# design.net
KiCad netlist of a schematic drawn in Altium Designer
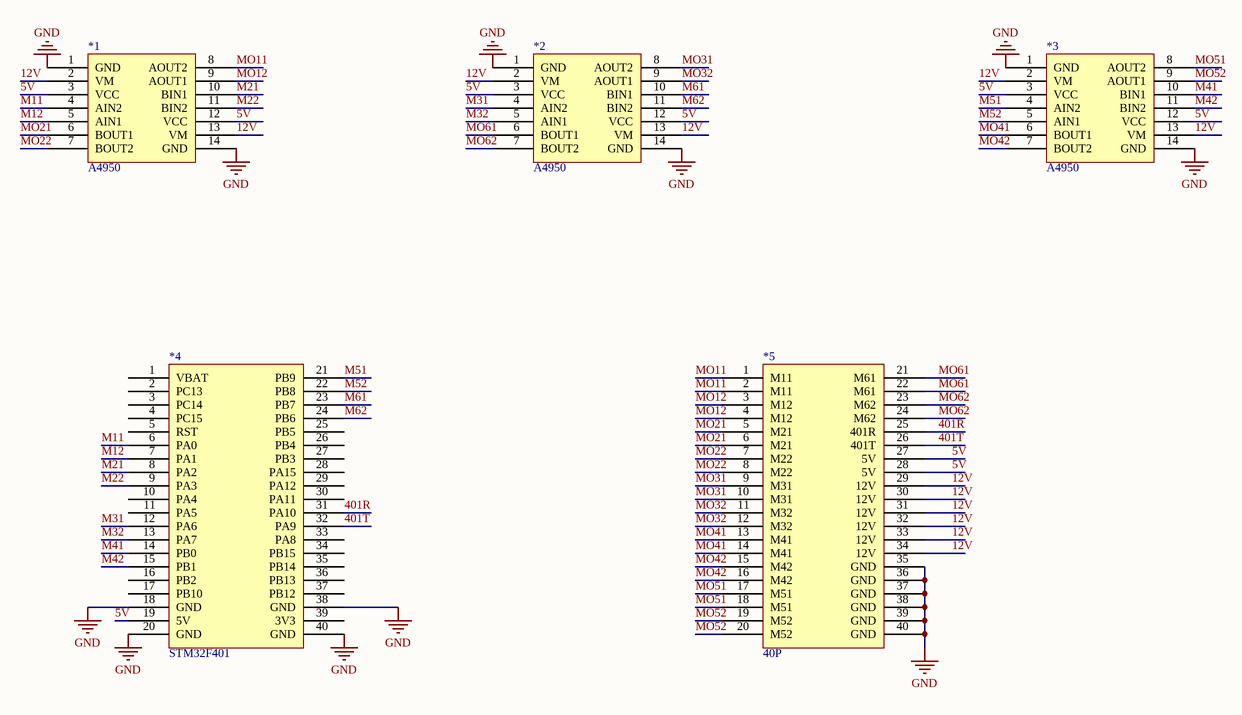
[diagram p0: 驱动板原理图.SchDoc]

(export (version "E")
  (design (tool "Eeschema 10.0.6"))
  (components
    (comp (ref "*1") (value "A4950") (footprint "A4950") (libsource (lib "Schlib1") (part "A4950")))
    (comp (ref "*2") (value "A4950") (footprint "A4950") (libsource (lib "Schlib1") (part "A4950")))
    (comp (ref "*3") (value "A4950") (footprint "A4950") (libsource (lib "Schlib1") (part "A4950")))
    (comp (ref "*4")
      (value "STM32F401")
      (footprint "STM32F401CCU6")
      (libsource (lib "Schlib1") (part "STM32F401"))
    )
    (comp (ref "*5") (value "40P") (footprint "PCBComponent_1") (libsource (lib "控制板原理图库") (part "40P")))
  )
  (nets
    (net (code "1") (name "/5V") (class "Default")
      (node (ref "*1") (pin "12") (pinfunction "VCC_12") (pintype "passive"))
      (node (ref "*1") (pin "3") (pinfunction "VCC_3") (pintype "passive"))
      (node (ref "*2") (pin "12") (pinfunction "VCC_12") (pintype "passive"))
      (node (ref "*2") (pin "3") (pinfunction "VCC_3") (pintype "passive"))
      (node (ref "*3") (pin "12") (pinfunction "VCC_12") (pintype "passive"))
      (node (ref "*3") (pin "3") (pinfunction "VCC_3") (pintype "passive"))
      (node (ref "*4") (pin "19") (pinfunction "5V_19") (pintype "passive"))
      (node (ref "*5") (pin "27") (pinfunction "5V_27") (pintype "passive"))
      (node (ref "*5") (pin "28") (pinfunction "5V_28") (pintype "passive"))
    )
    (net (code "2") (name "/12V") (class "Default")
      (node (ref "*1") (pin "13") (pinfunction "VM_13") (pintype "passive"))
      (node (ref "*1") (pin "2") (pinfunction "VM_2") (pintype "passive"))
      (node (ref "*2") (pin "13") (pinfunction "VM_13") (pintype "passive"))
      (node (ref "*2") (pin "2") (pinfunction "VM_2") (pintype "passive"))
      (node (ref "*3") (pin "13") (pinfunction "VM_13") (pintype "passive"))
      (node (ref "*3") (pin "2") (pinfunction "VM_2") (pintype "passive"))
      (node (ref "*5") (pin "29") (pinfunction "12V_29") (pintype "passive"))
      (node (ref "*5") (pin "30") (pinfunction "12V_30") (pintype "passive"))
      (node (ref "*5") (pin "31") (pinfunction "12V_31") (pintype "passive"))
      (node (ref "*5") (pin "32") (pinfunction "12V_32") (pintype "passive"))
      (node (ref "*5") (pin "33") (pinfunction "12V_33") (pintype "passive"))
      (node (ref "*5") (pin "34") (pinfunction "12V_34") (pintype "passive"))
    )
    (net (code "3") (name "/401R") (class "Default")
      (node (ref "*4") (pin "31") (pinfunction "PA10_31") (pintype "passive"))
      (node (ref "*5") (pin "25") (pinfunction "401R_25") (pintype "passive"))
    )
    (net (code "4") (name "/401T") (class "Default")
      (node (ref "*4") (pin "32") (pinfunction "PA9_32") (pintype "passive"))
      (node (ref "*5") (pin "26") (pinfunction "401T_26") (pintype "passive"))
    )
    (net (code "5") (name "/M11") (class "Default")
      (node (ref "*1") (pin "4") (pinfunction "AIN2_4") (pintype "passive"))
      (node (ref "*4") (pin "6") (pinfunction "PA0_6") (pintype "passive"))
    )
    (net (code "6") (name "/M12") (class "Default")
      (node (ref "*1") (pin "5") (pinfunction "AIN1_5") (pintype "passive"))
      (node (ref "*4") (pin "7") (pinfunction "PA1_7") (pintype "passive"))
    )
    (net (code "7") (name "/M21") (class "Default")
      (node (ref "*1") (pin "10") (pinfunction "BIN1_10") (pintype "passive"))
      (node (ref "*4") (pin "8") (pinfunction "PA2_8") (pintype "passive"))
    )
    (net (code "8") (name "/M22") (class "Default")
      (node (ref "*1") (pin "11") (pinfunction "BIN2_11") (pintype "passive"))
      (node (ref "*4") (pin "9") (pinfunction "PA3_9") (pintype "passive"))
    )
    (net (code "9") (name "/M31") (class "Default")
      (node (ref "*2") (pin "4") (pinfunction "AIN2_4") (pintype "passive"))
      (node (ref "*4") (pin "12") (pinfunction "PA6_12") (pintype "passive"))
    )
    (net (code "10") (name "/M32") (class "Default")
      (node (ref "*2") (pin "5") (pinfunction "AIN1_5") (pintype "passive"))
      (node (ref "*4") (pin "13") (pinfunction "PA7_13") (pintype "passive"))
    )
    (net (code "11") (name "/M41") (class "Default")
      (node (ref "*3") (pin "10") (pinfunction "BIN1_10") (pintype "passive"))
      (node (ref "*4") (pin "14") (pinfunction "PB0_14") (pintype "passive"))
    )
    (net (code "12") (name "/M42") (class "Default")
      (node (ref "*3") (pin "11") (pinfunction "BIN2_11") (pintype "passive"))
      (node (ref "*4") (pin "15") (pinfunction "PB1_15") (pintype "passive"))
    )
    (net (code "13") (name "/M51") (class "Default")
      (node (ref "*3") (pin "4") (pinfunction "AIN2_4") (pintype "passive"))
      (node (ref "*4") (pin "21") (pinfunction "PB9_21") (pintype "passive"))
    )
    (net (code "14") (name "/M52") (class "Default")
      (node (ref "*3") (pin "5") (pinfunction "AIN1_5") (pintype "passive"))
      (node (ref "*4") (pin "22") (pinfunction "PB8_22") (pintype "passive"))
    )
    (net (code "15") (name "/M61") (class "Default")
      (node (ref "*2") (pin "10") (pinfunction "BIN1_10") (pintype "passive"))
      (node (ref "*4") (pin "23") (pinfunction "PB7_23") (pintype "passive"))
    )
    (net (code "16") (name "/M62") (class "Default")
      (node (ref "*2") (pin "11") (pinfunction "BIN2_11") (pintype "passive"))
      (node (ref "*4") (pin "24") (pinfunction "PB6_24") (pintype "passive"))
    )
    (net (code "17") (name "/MO11") (class "Default")
      (node (ref "*1") (pin "8") (pinfunction "AOUT2_8") (pintype "passive"))
      (node (ref "*5") (pin "1") (pinfunction "M11_1") (pintype "passive"))
      (node (ref "*5") (pin "2") (pinfunction "M11_2") (pintype "passive"))
    )
    (net (code "18") (name "/MO12") (class "Default")
      (node (ref "*1") (pin "9") (pinfunction "AOUT1_9") (pintype "passive"))
      (node (ref "*5") (pin "3") (pinfunction "M12_3") (pintype "passive"))
      (node (ref "*5") (pin "4") (pinfunction "M12_4") (pintype "passive"))
    )
    (net (code "19") (name "/MO21") (class "Default")
      (node (ref "*1") (pin "6") (pinfunction "BOUT1_6") (pintype "passive"))
      (node (ref "*5") (pin "5") (pinfunction "M21_5") (pintype "passive"))
      (node (ref "*5") (pin "6") (pinfunction "M21_6") (pintype "passive"))
    )
    (net (code "20") (name "/MO22") (class "Default")
      (node (ref "*1") (pin "7") (pinfunction "BOUT2_7") (pintype "passive"))
      (node (ref "*5") (pin "7") (pinfunction "M22_7") (pintype "passive"))
      (node (ref "*5") (pin "8") (pinfunction "M22_8") (pintype "passive"))
    )
    (net (code "21") (name "/MO31") (class "Default")
      (node (ref "*2") (pin "8") (pinfunction "AOUT2_8") (pintype "passive"))
      (node (ref "*5") (pin "10") (pinfunction "M31_10") (pintype "passive"))
      (node (ref "*5") (pin "9") (pinfunction "M31_9") (pintype "passive"))
    )
    (net (code "22") (name "/MO32") (class "Default")
      (node (ref "*2") (pin "9") (pinfunction "AOUT1_9") (pintype "passive"))
      (node (ref "*5") (pin "11") (pinfunction "M32_11") (pintype "passive"))
      (node (ref "*5") (pin "12") (pinfunction "M32_12") (pintype "passive"))
    )
    (net (code "23") (name "/MO41") (class "Default")
      (node (ref "*3") (pin "6") (pinfunction "BOUT1_6") (pintype "passive"))
      (node (ref "*5") (pin "13") (pinfunction "M41_13") (pintype "passive"))
      (node (ref "*5") (pin "14") (pinfunction "M41_14") (pintype "passive"))
    )
    (net (code "24") (name "/MO42") (class "Default")
      (node (ref "*3") (pin "7") (pinfunction "BOUT2_7") (pintype "passive"))
      (node (ref "*5") (pin "15") (pinfunction "M42_15") (pintype "passive"))
      (node (ref "*5") (pin "16") (pinfunction "M42_16") (pintype "passive"))
    )
    (net (code "25") (name "/MO51") (class "Default")
      (node (ref "*3") (pin "8") (pinfunction "AOUT2_8") (pintype "passive"))
      (node (ref "*5") (pin "17") (pinfunction "M51_17") (pintype "passive"))
      (node (ref "*5") (pin "18") (pinfunction "M51_18") (pintype "passive"))
    )
    (net (code "26") (name "/MO52") (class "Default")
      (node (ref "*3") (pin "9") (pinfunction "AOUT1_9") (pintype "passive"))
      (node (ref "*5") (pin "19") (pinfunction "M52_19") (pintype "passive"))
      (node (ref "*5") (pin "20") (pinfunction "M52_20") (pintype "passive"))
    )
    (net (code "27") (name "/MO61") (class "Default")
      (node (ref "*2") (pin "6") (pinfunction "BOUT1_6") (pintype "passive"))
      (node (ref "*5") (pin "21") (pinfunction "M61_21") (pintype "passive"))
      (node (ref "*5") (pin "22") (pinfunction "M61_22") (pintype "passive"))
    )
    (net (code "28") (name "/MO62") (class "Default")
      (node (ref "*2") (pin "7") (pinfunction "BOUT2_7") (pintype "passive"))
      (node (ref "*5") (pin "23") (pinfunction "M62_23") (pintype "passive"))
      (node (ref "*5") (pin "24") (pinfunction "M62_24") (pintype "passive"))
    )
    (net (code "29") (name "GND") (class "Default")
      (node (ref "*1") (pin "1") (pinfunction "GND_1") (pintype "passive"))
      (node (ref "*1") (pin "14") (pinfunction "GND_14") (pintype "passive"))
      (node (ref "*2") (pin "1") (pinfunction "GND_1") (pintype "passive"))
      (node (ref "*2") (pin "14") (pinfunction "GND_14") (pintype "passive"))
      (node (ref "*3") (pin "1") (pinfunction "GND_1") (pintype "passive"))
      (node (ref "*3") (pin "14") (pinfunction "GND_14") (pintype "passive"))
      (node (ref "*4") (pin "18") (pinfunction "GND_18") (pintype "passive"))
      (node (ref "*4") (pin "20") (pinfunction "GND_20") (pintype "passive"))
      (node (ref "*4") (pin "38") (pinfunction "GND_38") (pintype "passive"))
      (node (ref "*4") (pin "40") (pinfunction "GND_40") (pintype "passive"))
      (node (ref "*5") (pin "35") (pinfunction "GND_35") (pintype "passive"))
      (node (ref "*5") (pin "36") (pinfunction "GND_36") (pintype "passive"))
      (node (ref "*5") (pin "37") (pinfunction "GND_37") (pintype "passive"))
      (node (ref "*5") (pin "38") (pinfunction "GND_38") (pintype "passive"))
      (node (ref "*5") (pin "39") (pinfunction "GND_39") (pintype "passive"))
      (node (ref "*5") (pin "40") (pinfunction "GND_40") (pintype "passive"))
    )
    (net (code "30") (name "unconnected-(*4-3V3-Pad39)") (class "Default")
      (node (ref "*4") (pin "39") (pinfunction "3V3_39") (pintype "passive"))
    )
    (net (code "31") (name "unconnected-(*4-PA4-Pad10)") (class "Default")
      (node (ref "*4") (pin "10") (pinfunction "PA4_10") (pintype "passive"))
    )
    (net (code "32") (name "unconnected-(*4-PA5-Pad11)") (class "Default")
      (node (ref "*4") (pin "11") (pinfunction "PA5_11") (pintype "passive"))
    )
    (net (code "33") (name "unconnected-(*4-PA8-Pad33)") (class "Default")
      (node (ref "*4") (pin "33") (pinfunction "PA8_33") (pintype "passive"))
    )
    (net (code "34") (name "unconnected-(*4-PA11-Pad30)") (class "Default")
      (node (ref "*4") (pin "30") (pinfunction "PA11_30") (pintype "passive"))
    )
    (net (code "35") (name "unconnected-(*4-PA12-Pad29)") (class "Default")
      (node (ref "*4") (pin "29") (pinfunction "PA12_29") (pintype "passive"))
    )
    (net (code "36") (name "unconnected-(*4-PA15-Pad28)") (class "Default")
      (node (ref "*4") (pin "28") (pinfunction "PA15_28") (pintype "passive"))
    )
    (net (code "37") (name "unconnected-(*4-PB2-Pad16)") (class "Default")
      (node (ref "*4") (pin "16") (pinfunction "PB2_16") (pintype "passive"))
    )
    (net (code "38") (name "unconnected-(*4-PB3-Pad27)") (class "Default")
      (node (ref "*4") (pin "27") (pinfunction "PB3_27") (pintype "passive"))
    )
    (net (code "39") (name "unconnected-(*4-PB4-Pad26)") (class "Default")
      (node (ref "*4") (pin "26") (pinfunction "PB4_26") (pintype "passive"))
    )
    (net (code "40") (name "unconnected-(*4-PB5-Pad25)") (class "Default")
      (node (ref "*4") (pin "25") (pinfunction "PB5_25") (pintype "passive"))
    )
    (net (code "41") (name "unconnected-(*4-PB10-Pad17)") (class "Default")
      (node (ref "*4") (pin "17") (pinfunction "PB10_17") (pintype "passive"))
    )
    (net (code "42") (name "unconnected-(*4-PB12-Pad37)") (class "Default")
      (node (ref "*4") (pin "37") (pinfunction "PB12_37") (pintype "passive"))
    )
    (net (code "43") (name "unconnected-(*4-PB13-Pad36)") (class "Default")
      (node (ref "*4") (pin "36") (pinfunction "PB13_36") (pintype "passive"))
    )
    (net (code "44") (name "unconnected-(*4-PB14-Pad35)") (class "Default")
      (node (ref "*4") (pin "35") (pinfunction "PB14_35") (pintype "passive"))
    )
    (net (code "45") (name "unconnected-(*4-PB15-Pad34)") (class "Default")
      (node (ref "*4") (pin "34") (pinfunction "PB15_34") (pintype "passive"))
    )
    (net (code "46") (name "unconnected-(*4-PC13-Pad2)") (class "Default")
      (node (ref "*4") (pin "2") (pinfunction "PC13_2") (pintype "passive"))
    )
    (net (code "47") (name "unconnected-(*4-PC14-Pad3)") (class "Default")
      (node (ref "*4") (pin "3") (pinfunction "PC14_3") (pintype "passive"))
    )
    (net (code "48") (name "unconnected-(*4-PC15-Pad4)") (class "Default")
      (node (ref "*4") (pin "4") (pinfunction "PC15_4") (pintype "passive"))
    )
    (net (code "49") (name "unconnected-(*4-RST-Pad5)") (class "Default")
      (node (ref "*4") (pin "5") (pinfunction "RST_5") (pintype "passive"))
    )
    (net (code "50") (name "unconnected-(*4-VBAT-Pad1)") (class "Default")
      (node (ref "*4") (pin "1") (pinfunction "VBAT_1") (pintype "passive"))
    )
  )
)
